# Sheet_2_Power.net
KiCad netlist of a schematic drawn in Altium Designer
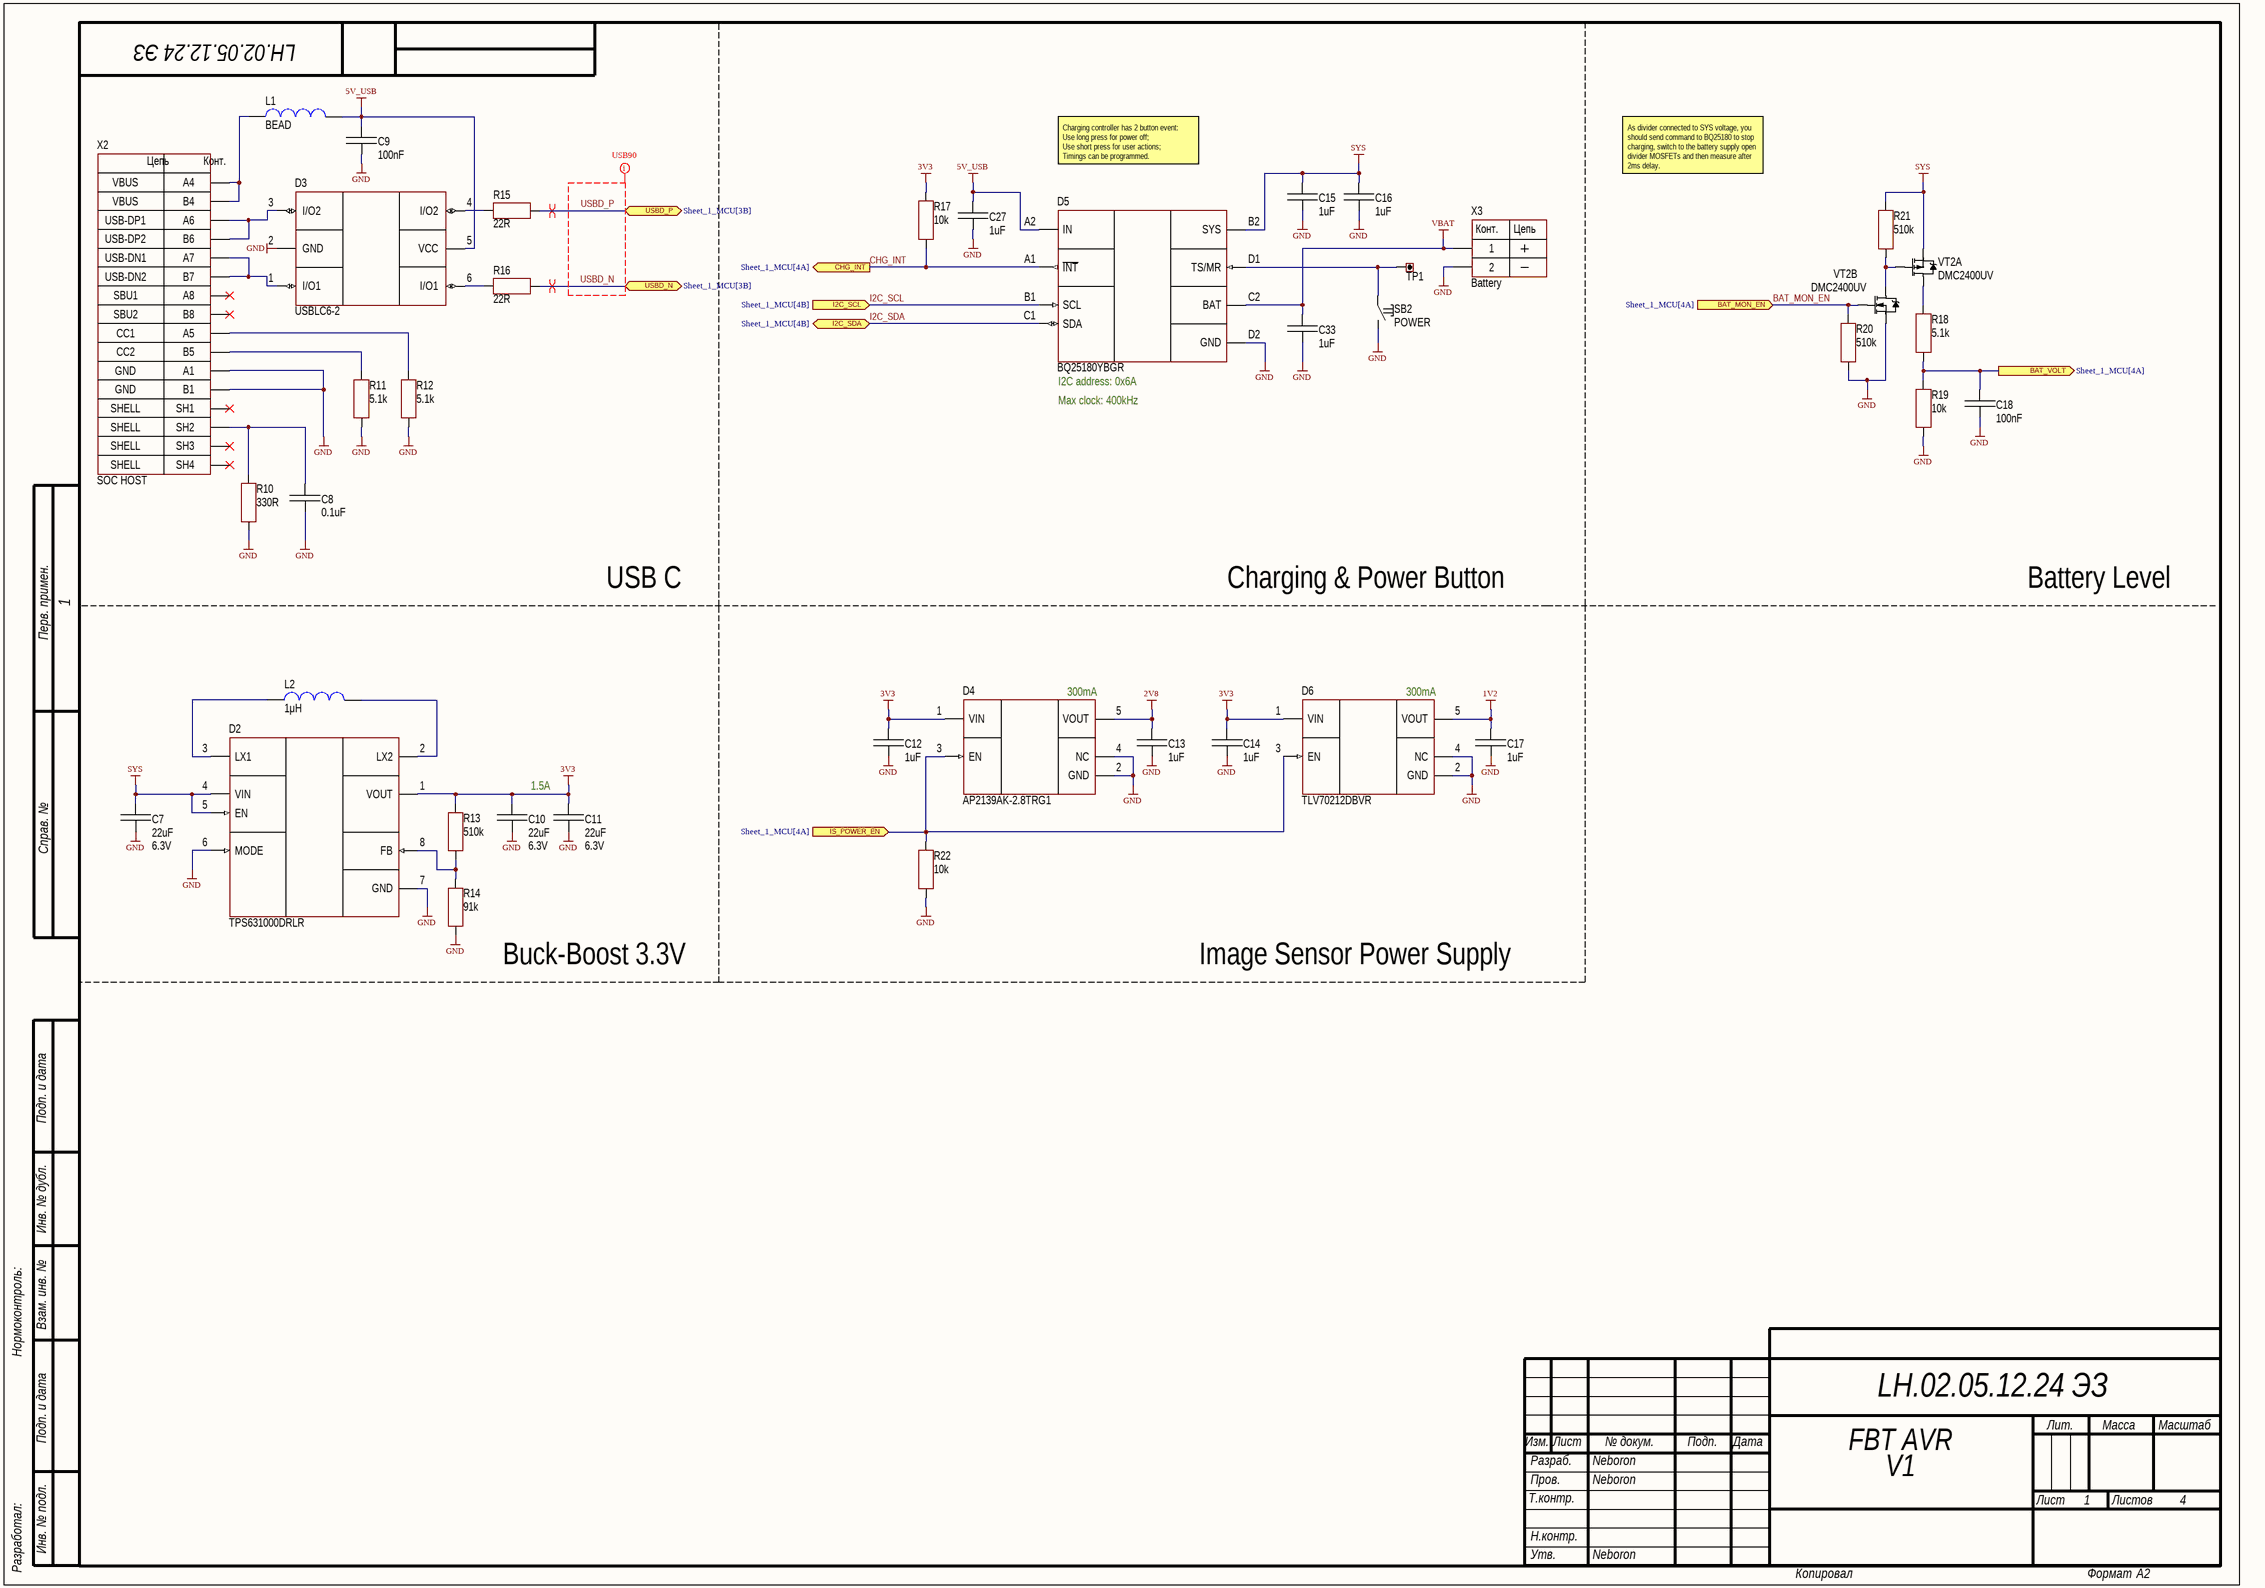
[diagram p0: Sheet_2_Power.SchDoc]

(export (version "E")
  (design (tool "Eeschema 10.0.6"))
  (components
    (comp (ref "C7")
      (value "22uF")
      (footprint "CAP: 0603")
      (fields
        (field (name "MANUFACTURER") "Any")
        (field (name "VALUEMANUFACTURERPARTNUMBER") "Ceramic capacitor, 22uF, X5R, ±10%, 6.3V, 0603, -55...+125°C")
        (field (name "TOLERANCE") "±10%")
        (field (name "VOLTAGE") "6.3V")
      )
      (libsource (lib "capacitor") (part "Ceramic_0603"))
    )
    (comp (ref "C8")
      (value "0.1uF")
      (footprint "CAP: 0603")
      (fields
        (field (name "MANUFACTURER") "Any")
        (field (name "VALUEMANUFACTURERPARTNUMBER") "Ceramic capacitor, 0.1uF, X7R, ±10%, 16V, 0603, -55...+125°C")
        (field (name "TOLERANCE") "±10%")
      )
      (libsource (lib "capacitor") (part "Ceramic_0603"))
    )
    (comp (ref "C9")
      (value "100nF")
      (footprint "CAP: 0402")
      (fields
        (field (name "MANUFACTURER") "Any")
        (field (name "VALUEMANUFACTURERPARTNUMBER") "Ceramic capacitor, 100nF, X7R, ±10%, 16V, 0402, -55...+125°C")
        (field (name "TOLERANCE") "±10%")
      )
      (libsource (lib "capacitor") (part "Ceramic_0402"))
    )
    (comp (ref "C10")
      (value "22uF")
      (footprint "CAP: 0603")
      (fields
        (field (name "MANUFACTURER") "Any")
        (field (name "VALUEMANUFACTURERPARTNUMBER") "Ceramic capacitor, 22uF, X5R, ±10%, 6.3V, 0603, -55...+125°C")
        (field (name "TOLERANCE") "±10%")
        (field (name "VOLTAGE") "6.3V")
      )
      (libsource (lib "capacitor") (part "Ceramic_0603"))
    )
    (comp (ref "C11")
      (value "22uF")
      (footprint "CAP: 0603")
      (fields
        (field (name "MANUFACTURER") "Any")
        (field (name "VALUEMANUFACTURERPARTNUMBER") "Ceramic capacitor, 22uF, X5R, ±10%, 6.3V, 0603, -55...+125°C")
        (field (name "TOLERANCE") "±10%")
        (field (name "VOLTAGE") "6.3V")
      )
      (libsource (lib "capacitor") (part "Ceramic_0603"))
    )
    (comp (ref "C12")
      (value "1uF")
      (footprint "CAP: 0402")
      (fields
        (field (name "MANUFACTURER") "Any")
        (field (name "VALUEMANUFACTURERPARTNUMBER") "Ceramic capacitor, 1uF, X7R, ±10%, 16V, 0402, -55...+125°C")
        (field (name "TOLERANCE") "±10%")
      )
      (libsource (lib "capacitor") (part "Ceramic_0402"))
    )
    (comp (ref "C13")
      (value "1uF")
      (footprint "CAP: 0402")
      (fields
        (field (name "MANUFACTURER") "Any")
        (field (name "VALUEMANUFACTURERPARTNUMBER") "Ceramic capacitor, 1uF, X7R, ±10%, 16V, 0402, -55...+125°C")
        (field (name "TOLERANCE") "±10%")
      )
      (libsource (lib "capacitor") (part "Ceramic_0402"))
    )
    (comp (ref "C14")
      (value "1uF")
      (footprint "CAP: 0402")
      (fields
        (field (name "MANUFACTURER") "Any")
        (field (name "VALUEMANUFACTURERPARTNUMBER") "Ceramic capacitor, 1uF, X7R, ±10%, 16V, 0402, -55...+125°C")
        (field (name "TOLERANCE") "±10%")
      )
      (libsource (lib "capacitor") (part "Ceramic_0402"))
    )
    (comp (ref "C15")
      (value "1uF")
      (footprint "CAP: 0402")
      (fields
        (field (name "MANUFACTURER") "Any")
        (field (name "VALUEMANUFACTURERPARTNUMBER") "Ceramic capacitor, 1uF, X7R, ±10%, 16V, 0402, -55...+125°C")
        (field (name "TOLERANCE") "±10%")
      )
      (libsource (lib "capacitor") (part "Ceramic_0402"))
    )
    (comp (ref "C16")
      (value "1uF")
      (footprint "CAP: 0402")
      (fields
        (field (name "MANUFACTURER") "Any")
        (field (name "VALUEMANUFACTURERPARTNUMBER") "Ceramic capacitor, 1uF, X7R, ±10%, 16V, 0402, -55...+125°C")
        (field (name "TOLERANCE") "±10%")
      )
      (libsource (lib "capacitor") (part "Ceramic_0402"))
    )
    (comp (ref "C17")
      (value "1uF")
      (footprint "CAP: 0402")
      (fields
        (field (name "MANUFACTURER") "Any")
        (field (name "VALUEMANUFACTURERPARTNUMBER") "Ceramic capacitor, 1uF, X7R, ±10%, 16V, 0402, -55...+125°C")
        (field (name "TOLERANCE") "±10%")
      )
      (libsource (lib "capacitor") (part "Ceramic_0402"))
    )
    (comp (ref "C18")
      (value "100nF")
      (footprint "CAP: 0402")
      (fields
        (field (name "MANUFACTURER") "Any")
        (field (name "VALUEMANUFACTURERPARTNUMBER") "Ceramic capacitor, 100nF, X7R, ±10%, 16V, 0402, -55...+125°C")
        (field (name "TOLERANCE") "±10%")
      )
      (libsource (lib "capacitor") (part "Ceramic_0402"))
    )
    (comp (ref "C27")
      (value "1uF")
      (footprint "CAP: 0402")
      (fields
        (field (name "MANUFACTURER") "Any")
        (field (name "VALUEMANUFACTURERPARTNUMBER") "Ceramic capacitor, 1uF, X7R, ±10%, 16V, 0402, -55...+125°C")
        (field (name "TOLERANCE") "±10%")
      )
      (libsource (lib "capacitor") (part "Ceramic_0402"))
    )
    (comp (ref "C33")
      (value "1uF")
      (footprint "CAP: 0402")
      (fields
        (field (name "MANUFACTURER") "Any")
        (field (name "VALUEMANUFACTURERPARTNUMBER") "Ceramic capacitor, 1uF, X7R, ±10%, 16V, 0402, -55...+125°C")
        (field (name "TOLERANCE") "±10%")
      )
      (libsource (lib "capacitor") (part "Ceramic_0402"))
    )
    (comp (ref "D2")
      (value "~")
      (footprint "SOT583-8")
      (description "Buck-boost converter")
      (fields
        (field (name "MANUFACTURER") "Texas Instruments")
        (field (name "VALUEMANUFACTURERPARTNUMBER") "DC/DC buck-boost converter, 1.6...5.5V, 2.4MHz, 1.2...5.3V, 1.5A, -40...+125°C, SOT-583")
        (field (name "PARTNUMBER") "TPS631000DRLR")
      )
      (libsource (lib "ic-power-supply") (part "TPS631000DRLR"))
    )
    (comp (ref "D3")
      (value "~")
      (footprint "SOT23-6")
      (description "ESD protection")
      (fields
        (field (name "MANUFACTURER") "STMicroelectronics")
        (field (name "VALUEMANUFACTURERPARTNUMBER") "ESD protection, , 8kV, , -40...+125°C, SOT23-6L")
        (field (name "PARTNUMBER") "USBLC6-2")
      )
      (libsource (lib "ic-interface") (part "USBLC6-2"))
    )
    (comp (ref "D4")
      (value "~")
      (footprint "SOT23-5")
      (description "Linear voltage regulator 2.8V")
      (fields
        (field (name "MANUFACTURER") "Diodes Incorporated")
        (field (name "VALUEMANUFACTURERPARTNUMBER") "Linear voltage regulator, 2.9...6V, 0.5V, 1.5V, 0.25A, -40...+85°C, SOT23-5")
        (field (name "PARTNUMBER") "AP2139AK-2.8TRG1")
      )
      (libsource (lib "ic-power-supply") (part "AP2139AK-2.8TRG1"))
    )
    (comp (ref "D5")
      (value "~")
      (footprint "8-DSBGA")
      (description "Charger")
      (fields
        (field (name "MANUFACTURER") "Texas Instruments")
        (field (name "VALUEMANUFACTURERPARTNUMBER") "Charger li-ion battery, input 4.35...26V, , 1A, -40...+125°C, 8-DSBGA")
        (field (name "PARTNUMBER") "BQ25180YBGR")
      )
      (libsource (lib "ic-power-supply") (part "BQ25180YBGR"))
    )
    (comp (ref "D6")
      (value "~")
      (footprint "SOT23-5")
      (description "Linear voltage regulator 1.2V")
      (fields
        (field (name "MANUFACTURER") "Texas Instruments")
        (field (name "VALUEMANUFACTURERPARTNUMBER") "Linear voltage regulator, 2...5.5V, 0.26V, 1.2V, 0.3A, -40...+85°C, SOT23-5")
        (field (name "PARTNUMBER") "TLV70212DBVR")
      )
      (libsource (lib "ic-power-supply") (part "TLV70212DBVR"))
    )
    (comp (ref "L1")
      (value "BEAD")
      (footprint "IND: 0402")
      (fields
        (field (name "MANUFACTURER") "Murata Electronics")
        (field (name "PARTNUMBER") "BLM15PX601SN1D")
        (field (name "VALUEMANUFACTURERPARTNUMBER") "Fixed inductor, BEAD, ±25%, 0402, 900mA, -55...+125°C")
      )
      (libsource (lib "inductor") (part "Inductor_0402"))
    )
    (comp (ref "L2")
      (value "1μH")
      (footprint "IND: 0805")
      (fields
        (field (name "MANUFACTURER") "Taiyo Yuden")
        (field (name "PARTNUMBER") "MAKK2016T1R0M")
        (field (name "VALUEMANUFACTURERPARTNUMBER") "Fixed inductor, 1μH, ±20%, 0805, 2.2A, -55...+125°C")
      )
      (libsource (lib "inductor") (part "Inductor_0805"))
    )
    (comp (ref "R10")
      (value "330R")
      (footprint "RES: 0603")
      (fields
        (field (name "MANUFACTURER") "Any")
        (field (name "VALUEMANUFACTURERPARTNUMBER") "Resistor film, 330R, ±5%, 0603, 0.1W, -55...+125°C")
        (field (name "POWER") "0.1W")
      )
      (libsource (lib "resistor") (part "Resistor_0603"))
    )
    (comp (ref "R11")
      (value "5.1k")
      (footprint "RES: 0402")
      (fields
        (field (name "MANUFACTURER") "Any")
        (field (name "VALUEMANUFACTURERPARTNUMBER") "Resistor film, 5.1k, ±5%, 0402, 0.063W, -55...+125°C")
        (field (name "POWER") "0.063W")
      )
      (libsource (lib "resistor") (part "Resistor_0402"))
    )
    (comp (ref "R12")
      (value "5.1k")
      (footprint "RES: 0402")
      (fields
        (field (name "MANUFACTURER") "Any")
        (field (name "VALUEMANUFACTURERPARTNUMBER") "Resistor film, 5.1k, ±5%, 0402, 0.063W, -55...+125°C")
        (field (name "POWER") "0.063W")
      )
      (libsource (lib "resistor") (part "Resistor_0402"))
    )
    (comp (ref "R13")
      (value "510k")
      (footprint "RES: 0402")
      (fields
        (field (name "MANUFACTURER") "Any")
        (field (name "VALUEMANUFACTURERPARTNUMBER") "Resistor film, 510k, ±5%, 0402, 0.063W, -55...+125°C")
        (field (name "POWER") "0.063W")
      )
      (libsource (lib "resistor") (part "Resistor_0402"))
    )
    (comp (ref "R14")
      (value "91k")
      (footprint "RES: 0402")
      (fields
        (field (name "MANUFACTURER") "Any")
        (field (name "VALUEMANUFACTURERPARTNUMBER") "Resistor film, 91k, ±5%, 0402, 0.063W, -55...+125°C")
        (field (name "POWER") "0.063W")
      )
      (libsource (lib "resistor") (part "Resistor_0402"))
    )
    (comp (ref "R15")
      (value "22R")
      (footprint "RES: 0402")
      (fields
        (field (name "MANUFACTURER") "Any")
        (field (name "VALUEMANUFACTURERPARTNUMBER") "Resistor film, 22R, ±5%, 0402, 0.063W, -55...+125°C")
        (field (name "POWER") "0.063W")
      )
      (libsource (lib "") (part "Resistor_0402_1"))
    )
    (comp (ref "R16")
      (value "22R")
      (footprint "RES: 0402")
      (fields
        (field (name "MANUFACTURER") "Any")
        (field (name "VALUEMANUFACTURERPARTNUMBER") "Resistor film, 22R, ±5%, 0402, 0.063W, -55...+125°C")
        (field (name "POWER") "0.063W")
      )
      (libsource (lib "") (part "Resistor_0402_1"))
    )
    (comp (ref "R17")
      (value "10k")
      (footprint "RES: 0402")
      (fields
        (field (name "MANUFACTURER") "Any")
        (field (name "VALUEMANUFACTURERPARTNUMBER") "Resistor film, 10k, ±5%, 0402, 0.063W, -55...+125°C")
        (field (name "POWER") "0.063W")
      )
      (libsource (lib "") (part "Resistor_0402_2"))
    )
    (comp (ref "R18")
      (value "5.1k")
      (footprint "RES: 0402")
      (fields
        (field (name "MANUFACTURER") "Any")
        (field (name "VALUEMANUFACTURERPARTNUMBER") "Resistor film, 5.1k, ±5%, 0402, 0.063W, -55...+125°C")
        (field (name "POWER") "0.063W")
      )
      (libsource (lib "resistor") (part "Resistor_0402"))
    )
    (comp (ref "R19")
      (value "10k")
      (footprint "RES: 0402")
      (fields
        (field (name "MANUFACTURER") "Any")
        (field (name "VALUEMANUFACTURERPARTNUMBER") "Resistor film, 10k, ±5%, 0402, 0.063W, -55...+125°C")
        (field (name "POWER") "0.063W")
      )
      (libsource (lib "resistor") (part "Resistor_0402"))
    )
    (comp (ref "R20")
      (value "510k")
      (footprint "RES: 0402")
      (fields
        (field (name "MANUFACTURER") "Any")
        (field (name "VALUEMANUFACTURERPARTNUMBER") "Resistor film, 510k, ±5%, 0402, 0.063W, -55...+125°C")
        (field (name "POWER") "0.063W")
      )
      (libsource (lib "resistor") (part "Resistor_0402"))
    )
    (comp (ref "R21")
      (value "510k")
      (footprint "RES: 0402")
      (fields
        (field (name "MANUFACTURER") "Any")
        (field (name "VALUEMANUFACTURERPARTNUMBER") "Resistor film, 510k, ±5%, 0402, 0.063W, -55...+125°C")
        (field (name "POWER") "0.063W")
      )
      (libsource (lib "resistor") (part "Resistor_0402"))
    )
    (comp (ref "R22")
      (value "10k")
      (footprint "RES: 0402")
      (fields
        (field (name "MANUFACTURER") "Any")
        (field (name "VALUEMANUFACTURERPARTNUMBER") "Resistor film, 10k, ±5%, 0402, 0.063W, -55...+125°C")
        (field (name "POWER") "0.063W")
      )
      (libsource (lib "") (part "Resistor_0402_2"))
    )
    (comp (ref "SB2")
      (value "~")
      (footprint "BUT: TS-1186F-B-A")
      (fields
        (field (name "MANUFACTURER") "XKB Connection")
        (field (name "VALUEMANUFACTURERPARTNUMBER") "Tactile button, TS-1186F")
        (field (name "PARTNUMBER") "TS-1186F-C-A")
        (field (name "COMMENTTEXT") "POWER")
      )
      (libsource (lib "electromechanics") (part "Button_tactile"))
    )
    (comp (ref "TP1")
      (value "~")
      (footprint "CON: TEST POINT 1 MM")
      (fields
        (field (name "MANUFACTURER") "Keystone")
        (field (name "VALUEMANUFACTURERPARTNUMBER") "Test point, Keystone, 5001")
        (field (name "PARTNUMBER") "5001")
      )
      (libsource (lib "connector") (part "Connector_Test_Point"))
    )
    (comp (ref "VT2")
      (value "~")
      (footprint "SOT563-6")
      (fields (field (name "MANUFACTURER") "Diodes Incorporated") (field (name "PARTNUMBER") "DMC2400UV"))
      (libsource (lib "transistor") (part "MOSFET_DUAL_NP_ISO"))
    )
    (comp (ref "X2")
      (value "~")
      (footprint "CON: TYPE-C-SOFNG MC-311S")
      (fields
        (field (name "MANUFACTURER") "GCT")
        (field (name "VALUEMANUFACTURERPARTNUMBER") "USB Type C, 5A")
        (field (name "PARTNUMBER") "TYPEC-304YSSW-ACP16")
        (field (name "COMMENTTEXT") "SOC HOST")
      )
      (libsource (lib "connector") (part "Connector_USB_Type_C"))
    )
    (comp (ref "X3")
      (value "~")
      (footprint "CON: BAT (2.00)")
      (fields
        (field (name "VALUEMANUFACTURERPARTNUMBER") "Connector, 2pin, 2mm, , ")
        (field (name "COMMENTTEXT") "Battery")
      )
      (libsource (lib "connector") (part "Connector_BAT-2"))
    )
  )
  (nets
    (net (code "1") (name "/BAT_MON_EN") (class "Default")
      (node (ref "R20") (pin "2") (pinfunction "2_2") (pintype "passive"))
      (node (ref "VT2") (pin "2") (pinfunction "2_2") (pintype "passive"))
    )
    (net (code "2") (name "/BAT_VOLT") (class "Default")
      (node (ref "C18") (pin "2") (pinfunction "2_2") (pintype "passive"))
      (node (ref "R18") (pin "1") (pinfunction "1_1") (pintype "passive"))
      (node (ref "R19") (pin "2") (pinfunction "2_2") (pintype "passive"))
    )
    (net (code "3") (name "/CHG_INT") (class "Default")
      (node (ref "D5") (pin "A1") (pinfunction "~{INT}_A1") (pintype "output"))
      (node (ref "R17") (pin "2") (pinfunction "2_2") (pintype "passive"))
    )
    (net (code "4") (name "/I2C_SCL") (class "Default")
      (node (ref "D5") (pin "B1") (pinfunction "SCL_B1") (pintype "input"))
    )
    (net (code "5") (name "/I2C_SDA") (class "Default")
      (node (ref "D5") (pin "C1") (pinfunction "SDA_C1") (pintype "bidirectional"))
    )
    (net (code "6") (name "/IS_POWER_EN") (class "Default")
      (node (ref "D4") (pin "3") (pinfunction "EN_3") (pintype "input"))
      (node (ref "D6") (pin "3") (pinfunction "EN_3") (pintype "input"))
      (node (ref "R22") (pin "1") (pinfunction "1_1") (pintype "passive"))
    )
    (net (code "7") (name "/USBD_N") (class "Default")
      (node (ref "R16") (pin "1") (pinfunction "1_1") (pintype "passive"))
    )
    (net (code "8") (name "/USBD_P") (class "Default")
      (node (ref "R15") (pin "1") (pinfunction "1_1") (pintype "passive"))
    )
    (net (code "9") (name "1V2") (class "Default")
      (node (ref "C17") (pin "1") (pinfunction "1_1") (pintype "passive"))
      (node (ref "D6") (pin "5") (pinfunction "VOUT_5") (pintype "power_in"))
    )
    (net (code "10") (name "2V8") (class "Default")
      (node (ref "C13") (pin "1") (pinfunction "1_1") (pintype "passive"))
      (node (ref "D4") (pin "5") (pinfunction "VOUT_5") (pintype "power_in"))
    )
    (net (code "11") (name "3V3") (class "Default")
      (node (ref "C10") (pin "2") (pinfunction "2_2") (pintype "passive"))
      (node (ref "C11") (pin "2") (pinfunction "2_2") (pintype "passive"))
      (node (ref "C12") (pin "1") (pinfunction "1_1") (pintype "passive"))
      (node (ref "C14") (pin "1") (pinfunction "1_1") (pintype "passive"))
      (node (ref "D2") (pin "1") (pinfunction "VOUT_1") (pintype "power_in"))
      (node (ref "D4") (pin "1") (pinfunction "VIN_1") (pintype "power_in"))
      (node (ref "D6") (pin "1") (pinfunction "VIN_1") (pintype "power_in"))
      (node (ref "R13") (pin "2") (pinfunction "2_2") (pintype "passive"))
      (node (ref "R17") (pin "1") (pinfunction "1_1") (pintype "passive"))
    )
    (net (code "12") (name "5V_USB") (class "Default")
      (node (ref "C27") (pin "1") (pinfunction "1_1") (pintype "passive"))
      (node (ref "C9") (pin "1") (pinfunction "1_1") (pintype "passive"))
      (node (ref "D3") (pin "5") (pinfunction "VCC_5") (pintype "power_in"))
      (node (ref "D5") (pin "A2") (pinfunction "IN_A2") (pintype "power_in"))
      (node (ref "L1") (pin "1") (pinfunction "1_1") (pintype "passive"))
    )
    (net (code "13") (name "GND") (class "Default")
      (node (ref "C10") (pin "1") (pinfunction "1_1") (pintype "passive"))
      (node (ref "C11") (pin "1") (pinfunction "1_1") (pintype "passive"))
      (node (ref "C12") (pin "2") (pinfunction "2_2") (pintype "passive"))
      (node (ref "C13") (pin "2") (pinfunction "2_2") (pintype "passive"))
      (node (ref "C14") (pin "2") (pinfunction "2_2") (pintype "passive"))
      (node (ref "C15") (pin "2") (pinfunction "2_2") (pintype "passive"))
      (node (ref "C16") (pin "2") (pinfunction "2_2") (pintype "passive"))
      (node (ref "C17") (pin "2") (pinfunction "2_2") (pintype "passive"))
      (node (ref "C18") (pin "1") (pinfunction "1_1") (pintype "passive"))
      (node (ref "C27") (pin "2") (pinfunction "2_2") (pintype "passive"))
      (node (ref "C33") (pin "2") (pinfunction "2_2") (pintype "passive"))
      (node (ref "C7") (pin "1") (pinfunction "1_1") (pintype "passive"))
      (node (ref "C8") (pin "2") (pinfunction "2_2") (pintype "passive"))
      (node (ref "C9") (pin "2") (pinfunction "2_2") (pintype "passive"))
      (node (ref "D2") (pin "6") (pinfunction "MODE_6") (pintype "input"))
      (node (ref "D2") (pin "7") (pinfunction "GND_7") (pintype "passive"))
      (node (ref "D3") (pin "2") (pinfunction "GND_2") (pintype "power_in"))
      (node (ref "D4") (pin "2") (pinfunction "GND_2") (pintype "power_in"))
      (node (ref "D4") (pin "4") (pinfunction "NC_4") (pintype "passive"))
      (node (ref "D5") (pin "D2") (pinfunction "GND_D2") (pintype "power_in"))
      (node (ref "D6") (pin "2") (pinfunction "GND_2") (pintype "power_in"))
      (node (ref "D6") (pin "4") (pinfunction "NC_4") (pintype "passive"))
      (node (ref "R10") (pin "1") (pinfunction "1_1") (pintype "passive"))
      (node (ref "R11") (pin "1") (pinfunction "1_1") (pintype "passive"))
      (node (ref "R12") (pin "1") (pinfunction "1_1") (pintype "passive"))
      (node (ref "R14") (pin "1") (pinfunction "1_1") (pintype "passive"))
      (node (ref "R19") (pin "1") (pinfunction "1_1") (pintype "passive"))
      (node (ref "R20") (pin "1") (pinfunction "1_1") (pintype "passive"))
      (node (ref "R22") (pin "2") (pinfunction "2_2") (pintype "passive"))
      (node (ref "SB2") (pin "2") (pinfunction "2_2") (pintype "passive"))
      (node (ref "VT2") (pin "1") (pinfunction "1_1") (pintype "passive"))
      (node (ref "X2") (pin "A1") (pinfunction "A1_A1") (pintype "power_in"))
      (node (ref "X2") (pin "B1") (pinfunction "B1_B1") (pintype "power_in"))
      (node (ref "X3") (pin "2") (pinfunction "2_2") (pintype "passive"))
    )
    (net (code "14") (name "Net-(C8-Pad1)") (class "Default")
      (node (ref "C8") (pin "1") (pinfunction "1_1") (pintype "passive"))
      (node (ref "R10") (pin "2") (pinfunction "2_2") (pintype "passive"))
      (node (ref "X2") (pin "SH2") (pinfunction "SH2_SH2") (pintype "power_in"))
    )
    (net (code "15") (name "Net-(D2-FB)") (class "Default")
      (node (ref "D2") (pin "8") (pinfunction "FB_8") (pintype "input"))
      (node (ref "R13") (pin "1") (pinfunction "1_1") (pintype "passive"))
      (node (ref "R14") (pin "2") (pinfunction "2_2") (pintype "passive"))
    )
    (net (code "16") (name "Net-(D2-LX1)") (class "Default")
      (node (ref "D2") (pin "3") (pinfunction "LX1_3") (pintype "passive"))
      (node (ref "L2") (pin "2") (pinfunction "2_2") (pintype "passive"))
    )
    (net (code "17") (name "Net-(D2-LX2)") (class "Default")
      (node (ref "D2") (pin "2") (pinfunction "LX2_2") (pintype "passive"))
      (node (ref "L2") (pin "1") (pinfunction "1_1") (pintype "passive"))
    )
    (net (code "18") (name "Net-(D3-I{slash}O1-Pad1)") (class "Default")
      (node (ref "D3") (pin "1") (pinfunction "I/O1_1") (pintype "bidirectional"))
      (node (ref "X2") (pin "A7") (pinfunction "A7_A7") (pintype "power_in"))
      (node (ref "X2") (pin "B7") (pinfunction "B7_B7") (pintype "power_in"))
    )
    (net (code "19") (name "Net-(D3-I{slash}O1-Pad6)") (class "Default")
      (node (ref "D3") (pin "6") (pinfunction "I/O1_6") (pintype "bidirectional"))
      (node (ref "R16") (pin "2") (pinfunction "2_2") (pintype "passive"))
    )
    (net (code "20") (name "Net-(D3-I{slash}O2-Pad3)") (class "Default")
      (node (ref "D3") (pin "3") (pinfunction "I/O2_3") (pintype "bidirectional"))
      (node (ref "X2") (pin "A6") (pinfunction "A6_A6") (pintype "power_in"))
      (node (ref "X2") (pin "B6") (pinfunction "B6_B6") (pintype "power_in"))
    )
    (net (code "21") (name "Net-(D3-I{slash}O2-Pad4)") (class "Default")
      (node (ref "D3") (pin "4") (pinfunction "I/O2_4") (pintype "bidirectional"))
      (node (ref "R15") (pin "2") (pinfunction "2_2") (pintype "passive"))
    )
    (net (code "22") (name "Net-(D5-TS{slash}MR)") (class "Default")
      (node (ref "D5") (pin "D1") (pinfunction "TS/MR_D1") (pintype "input"))
      (node (ref "SB2") (pin "1") (pinfunction "1_1") (pintype "passive"))
      (node (ref "TP1") (pin "1") (pinfunction "1_1") (pintype "passive"))
    )
    (net (code "23") (name "Net-(L1-Pad2)") (class "Default")
      (node (ref "L1") (pin "2") (pinfunction "2_2") (pintype "passive"))
      (node (ref "X2") (pin "A4") (pinfunction "A4_A4") (pintype "passive"))
      (node (ref "X2") (pin "B4") (pinfunction "B4_B4") (pintype "passive"))
    )
    (net (code "24") (name "Net-(R11-Pad2)") (class "Default")
      (node (ref "R11") (pin "2") (pinfunction "2_2") (pintype "passive"))
      (node (ref "X2") (pin "B5") (pinfunction "B5_B5") (pintype "power_in"))
    )
    (net (code "25") (name "Net-(R12-Pad2)") (class "Default")
      (node (ref "R12") (pin "2") (pinfunction "2_2") (pintype "passive"))
      (node (ref "X2") (pin "A5") (pinfunction "A5_A5") (pintype "power_in"))
    )
    (net (code "26") (name "Net-(R18-Pad2)") (class "Default")
      (node (ref "R18") (pin "2") (pinfunction "2_2") (pintype "passive"))
      (node (ref "VT2") (pin "3") (pinfunction "3_3") (pintype "passive"))
    )
    (net (code "27") (name "Net-(R21-Pad1)") (class "Default")
      (node (ref "R21") (pin "1") (pinfunction "1_1") (pintype "passive"))
      (node (ref "VT2") (pin "5") (pinfunction "5_5") (pintype "passive"))
      (node (ref "VT2") (pin "6") (pinfunction "6_6") (pintype "passive"))
    )
    (net (code "28") (name "SYS") (class "Default")
      (node (ref "C15") (pin "1") (pinfunction "1_1") (pintype "passive"))
      (node (ref "C16") (pin "1") (pinfunction "1_1") (pintype "passive"))
      (node (ref "C7") (pin "2") (pinfunction "2_2") (pintype "passive"))
      (node (ref "D2") (pin "4") (pinfunction "VIN_4") (pintype "power_in"))
      (node (ref "D2") (pin "5") (pinfunction "EN_5") (pintype "input"))
      (node (ref "D5") (pin "B2") (pinfunction "SYS_B2") (pintype "power_in"))
      (node (ref "R21") (pin "2") (pinfunction "2_2") (pintype "passive"))
      (node (ref "VT2") (pin "4") (pinfunction "4_4") (pintype "passive"))
    )
    (net (code "29") (name "VBAT") (class "Default")
      (node (ref "C33") (pin "1") (pinfunction "1_1") (pintype "passive"))
      (node (ref "D5") (pin "C2") (pinfunction "BAT_C2") (pintype "power_in"))
      (node (ref "X3") (pin "1") (pinfunction "1_1") (pintype "passive"))
    )
    (net (code "30") (name "unconnected-(X2-PadA8)") (class "Default")
      (node (ref "X2") (pin "A8") (pinfunction "A8_A8") (pintype "power_in+no_connect"))
    )
    (net (code "31") (name "unconnected-(X2-PadB8)") (class "Default")
      (node (ref "X2") (pin "B8") (pinfunction "B8_B8") (pintype "power_in+no_connect"))
    )
    (net (code "32") (name "unconnected-(X2-PadSH1)") (class "Default")
      (node (ref "X2") (pin "SH1") (pinfunction "SH1_SH1") (pintype "power_in+no_connect"))
    )
    (net (code "33") (name "unconnected-(X2-PadSH3)") (class "Default")
      (node (ref "X2") (pin "SH3") (pinfunction "SH3_SH3") (pintype "power_in+no_connect"))
    )
    (net (code "34") (name "unconnected-(X2-PadSH4)") (class "Default")
      (node (ref "X2") (pin "SH4") (pinfunction "SH4_SH4") (pintype "power_in+no_connect"))
    )
  )
)
